# MC_stm32.net
KiCad netlist of a schematic drawn in Altium Designer
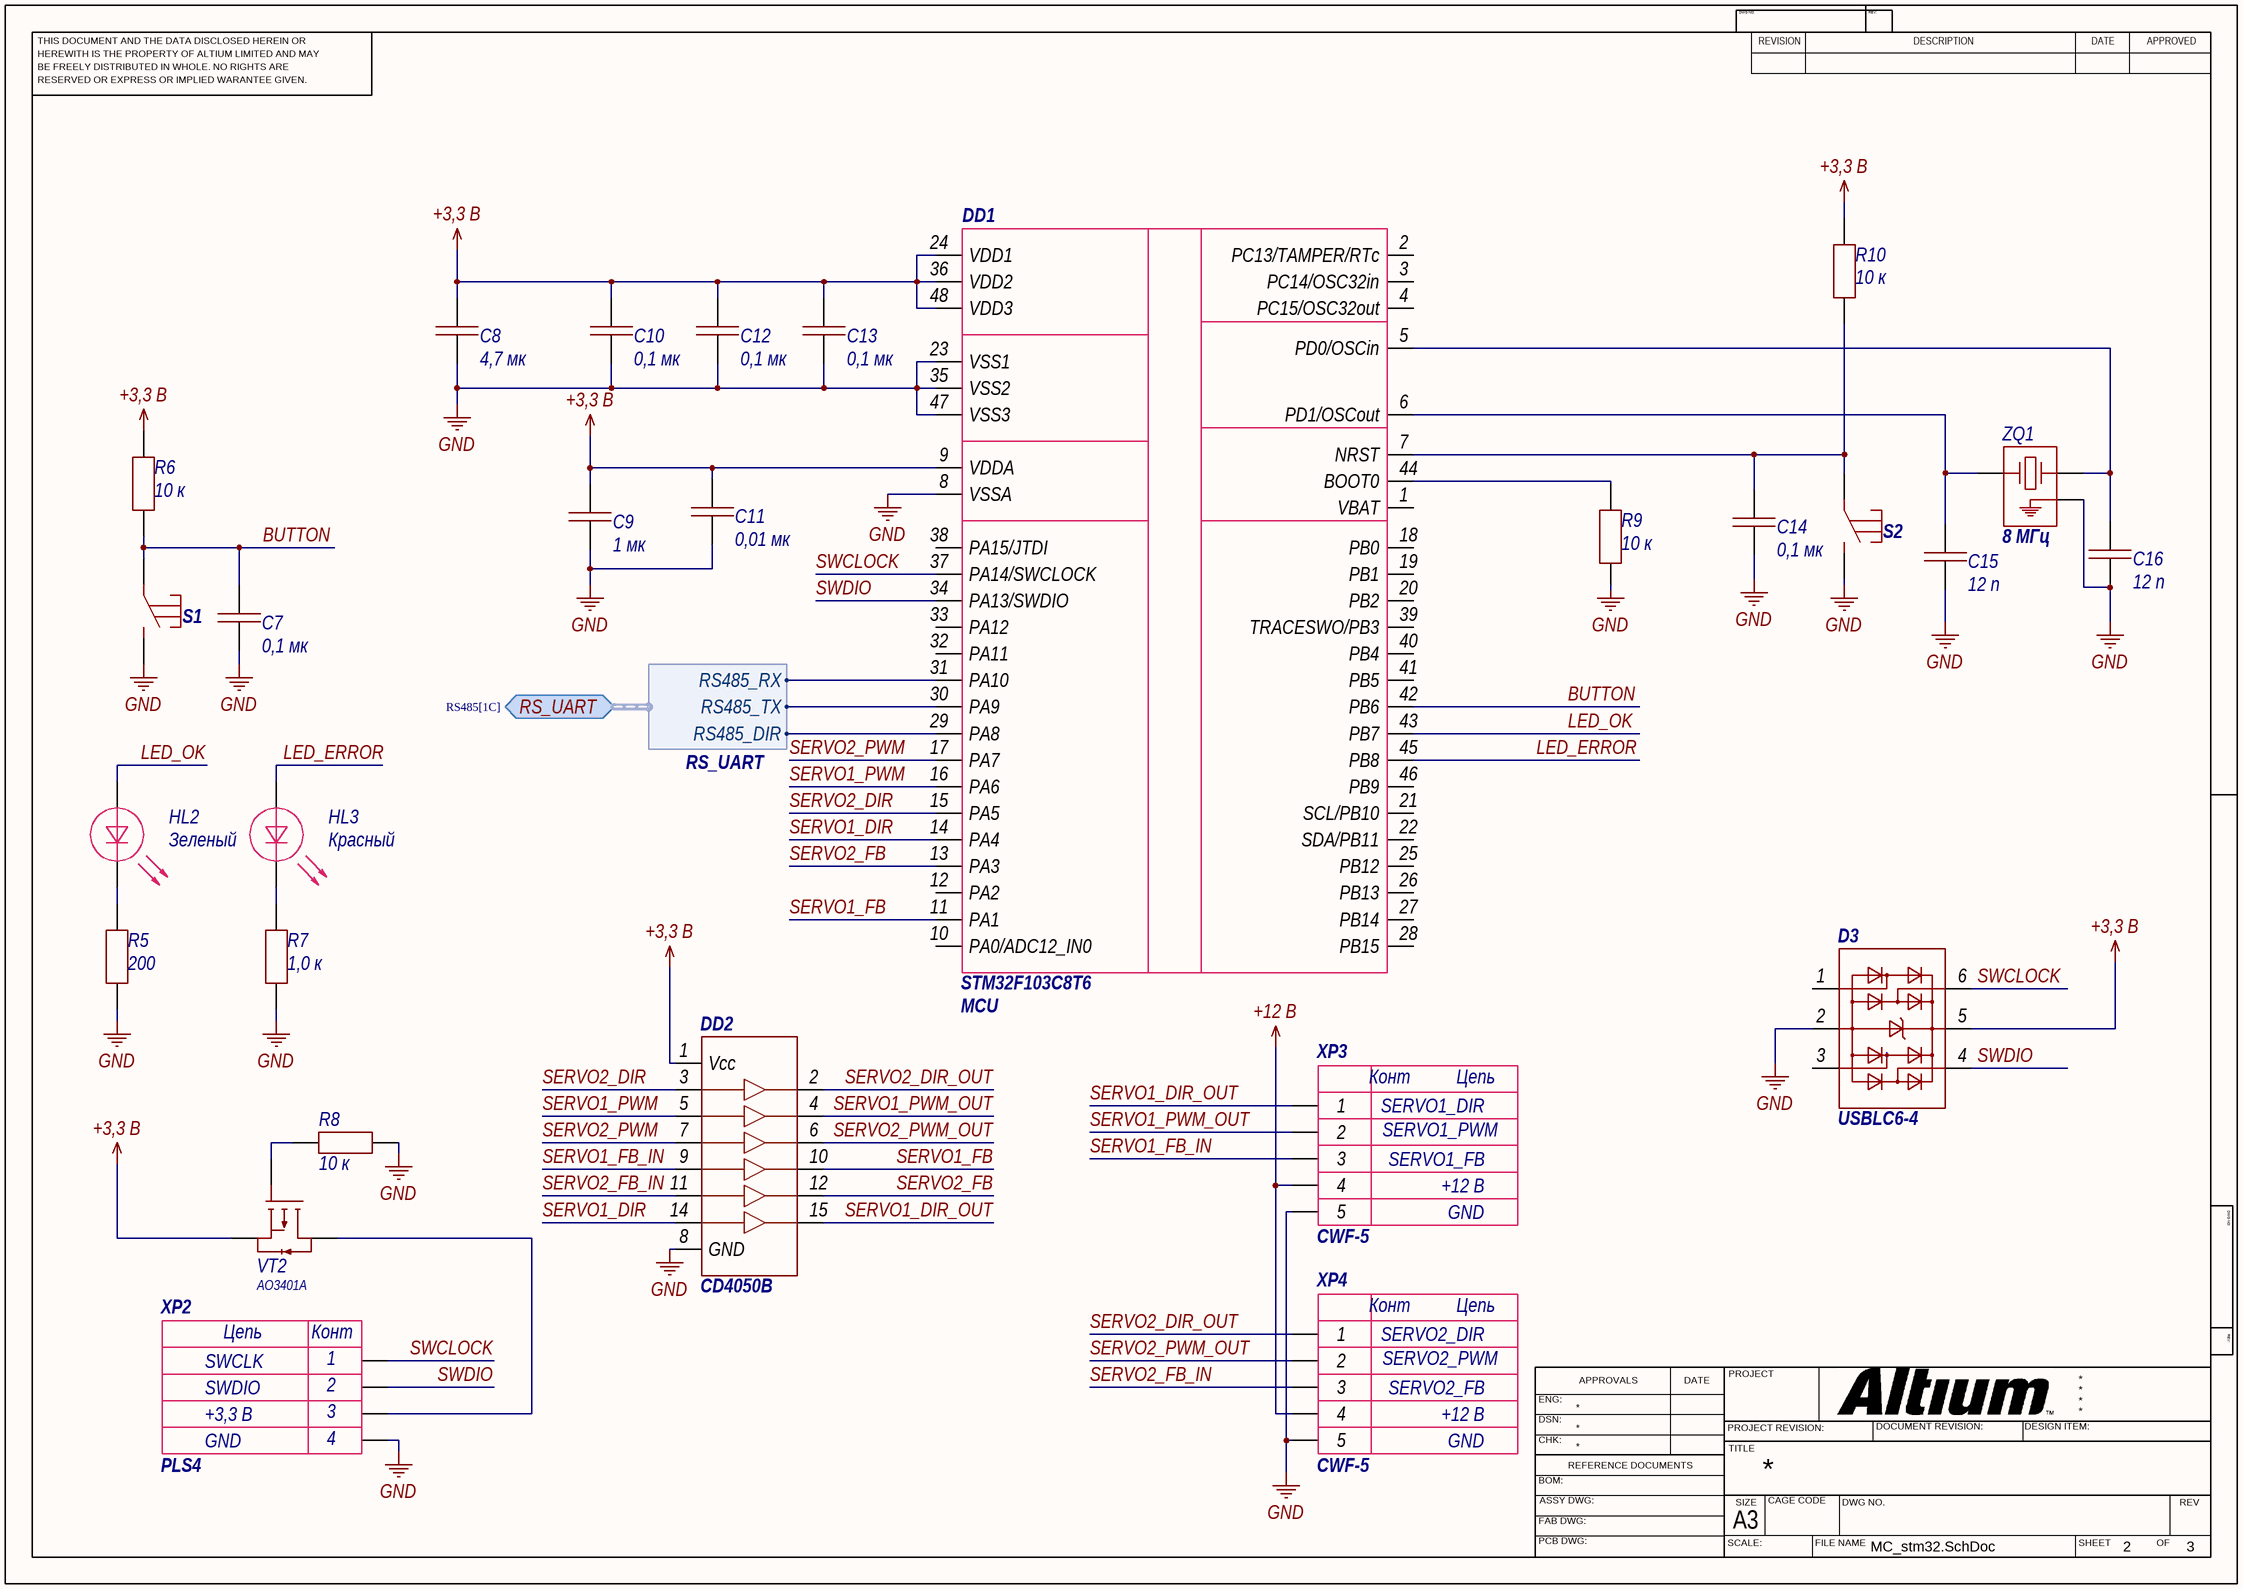
[diagram p0: MC_stm32.SchDoc]

(export (version "E")
  (design (tool "Eeschema 10.0.6"))
  (components
    (comp (ref "C7")
      (value "0,1 мк")
      (footprint "0603C")
      (description "Конденсатор")
      (fields (field (name "PART NUMBER") "Capacitor_0,1u_10_50V_X7R_0603C") (field (name "TOLERANCE") "0,1"))
      (libsource (lib "Hydrolib") (part "Capacitor"))
    )
    (comp (ref "C8")
      (value "4,7 мк")
      (footprint "1206C")
      (description "Конденсатор")
      (fields (field (name "PART NUMBER") "Capacitor_4,7u_10_50V_X7R_1206C") (field (name "TOLERANCE") "0,1"))
      (libsource (lib "Hydrolib") (part "Capacitor"))
    )
    (comp (ref "C9")
      (value "1 мк")
      (footprint "0603C")
      (description "Конденсатор")
      (fields (field (name "PART NUMBER") "Capacitor_1u_10_50V_X7R_0603C") (field (name "TOLERANCE") "0,1"))
      (libsource (lib "Hydrolib") (part "Capacitor"))
    )
    (comp (ref "C10")
      (value "0,1 мк")
      (footprint "0603C")
      (description "Конденсатор")
      (fields (field (name "PART NUMBER") "Capacitor_0,1u_10_50V_X7R_0603C") (field (name "TOLERANCE") "0,1"))
      (libsource (lib "Hydrolib") (part "Capacitor"))
    )
    (comp (ref "C11")
      (value "0,01 мк")
      (footprint "0603C")
      (description "Конденсатор")
      (fields (field (name "PART NUMBER") "Capacitor_10n_10_50V_X7R_0603C") (field (name "TOLERANCE") "0,1"))
      (libsource (lib "Hydrolib") (part "Capacitor"))
    )
    (comp (ref "C12")
      (value "0,1 мк")
      (footprint "0603C")
      (description "Конденсатор")
      (fields (field (name "PART NUMBER") "Capacitor_0,1u_10_50V_X7R_0603C") (field (name "TOLERANCE") "0,1"))
      (libsource (lib "Hydrolib") (part "Capacitor"))
    )
    (comp (ref "C13")
      (value "0,1 мк")
      (footprint "0603C")
      (description "Конденсатор")
      (fields (field (name "PART NUMBER") "Capacitor_0,1u_10_50V_X7R_0603C") (field (name "TOLERANCE") "0,1"))
      (libsource (lib "Hydrolib") (part "Capacitor"))
    )
    (comp (ref "C14")
      (value "0,1 мк")
      (footprint "0603C")
      (description "Конденсатор")
      (fields (field (name "PART NUMBER") "Capacitor_0,1u_10_50V_X7R_0603C") (field (name "TOLERANCE") "0,1"))
      (libsource (lib "Hydrolib") (part "Capacitor"))
    )
    (comp (ref "C15")
      (value "12 п")
      (footprint "0603C")
      (description "Конденсатор")
      (fields (field (name "PART NUMBER") "Capacitor"))
      (libsource (lib "Hydrolib") (part "Capacitor"))
    )
    (comp (ref "C16")
      (value "12 п")
      (footprint "0603C")
      (description "Конденсатор")
      (fields (field (name "PART NUMBER") "Capacitor"))
      (libsource (lib "Hydrolib") (part "Capacitor"))
    )
    (comp (ref "D3")
      (value "USBLC6-4")
      (footprint "SOT23-6")
      (description "Сборка защитных диодов для USB")
      (libsource (lib "Hydrolib") (part "USBLC6-4"))
    )
    (comp (ref "DD1")
      (value "STM32F103C8T6")
      (footprint "LQFP48")
      (description "Микроконтроллер")
      (fields (field (name "MANUFACTURER") "ST Microelectronics") (field (name "VALUE1") "MCU"))
      (libsource (lib "Hydrolib") (part "STM32F103C8T6"))
    )
    (comp (ref "DD2")
      (value "CD4050B")
      (footprint "SOIC-16")
      (description "Шесть буферных элементов")
      (libsource (lib "Hydrolib") (part "CD4050B"))
    )
    (comp (ref "HL2")
      (value "LED")
      (footprint "0805D")
      (description "Светодиод")
      (fields (field (name "COLOR") "Зеленый"))
      (libsource (lib "Hydrolib") (part "LED"))
    )
    (comp (ref "HL3")
      (value "LED")
      (footprint "0805D")
      (description "Светодиод")
      (fields (field (name "COLOR") "Красный"))
      (libsource (lib "Hydrolib") (part "LED"))
    )
    (comp (ref "R5")
      (value "200")
      (footprint "0603R")
      (description "Резистор номиналом 200 Ом и точностью 1%")
      (fields (field (name "PART NUMBER") "Resistor_200_1_0603") (field (name "TOLERANCE") "1%"))
      (libsource (lib "") (part "Resistor_1"))
    )
    (comp (ref "R6")
      (value "10 к")
      (footprint "0603R")
      (description "Резистор номиналом 10 кОм и точностью 1%")
      (fields (field (name "PART NUMBER") "Resistor_10k_1_0603") (field (name "TOLERANCE") "1%"))
      (libsource (lib "") (part "Resistor_1"))
    )
    (comp (ref "R7")
      (value "1,0 к")
      (footprint "0603R")
      (description "Резистор номиналом 1,0 кОм и точностью 1%")
      (fields (field (name "PART NUMBER") "Resistor_1.0k_1_0603") (field (name "TOLERANCE") "1%"))
      (libsource (lib "") (part "Resistor_1"))
    )
    (comp (ref "R8")
      (value "10 к")
      (footprint "0603R")
      (description "Резистор номиналом 10 кОм и точностью 1%")
      (fields (field (name "PART NUMBER") "Resistor_10k_1_0603") (field (name "TOLERANCE") "1%"))
      (libsource (lib "Hydrolib") (part "Resistor"))
    )
    (comp (ref "R9")
      (value "10 к")
      (footprint "0603R")
      (description "Резистор номиналом 10 кОм и точностью 1%")
      (fields (field (name "PART NUMBER") "Resistor_10k_1_0603") (field (name "TOLERANCE") "1%"))
      (libsource (lib "") (part "Resistor_1"))
    )
    (comp (ref "R10")
      (value "10 к")
      (footprint "0603R")
      (description "Резистор номиналом 10 кОм и точностью 1%")
      (fields (field (name "PART NUMBER") "Resistor_10k_1_0603") (field (name "TOLERANCE") "1%"))
      (libsource (lib "") (part "Resistor_2"))
    )
    (comp (ref "S1")
      (value "Tact_button")
      (footprint "Button_SMD_10mm")
      (description "Тактовая кнопка")
      (libsource (lib "Hydrolib") (part "Tact_button"))
    )
    (comp (ref "S2")
      (value "Tact_button")
      (footprint "Button_SMD_10mm")
      (description "Тактовая кнопка")
      (libsource (lib "Hydrolib") (part "Tact_button"))
    )
    (comp (ref "VT2")
      (value "AO3401A")
      (footprint "SOT23-3")
      (description "P-канальный MOSFET")
      (libsource (lib "Hydrolib") (part "MOSFET P-channel 2"))
    )
    (comp (ref "XP2")
      (value "PLS4")
      (footprint "PLS4")
      (description "Гребенка 4 пина")
      (fields
        (field (name "VALUE3") "+3,3 В")
        (field (name "VALUE2") "SWDIO")
        (field (name "VALUE4") "GND")
        (field (name "VALUE1") "SWCLK")
      )
      (libsource (lib "Hydrolib") (part "Conn_4pin"))
    )
    (comp (ref "XP3")
      (value "CWF-5")
      (footprint "CWF-5")
      (description "5-пиновый разъем с ключом")
      (fields
        (field (name "SERVO1_DIR") "SERVO1_DIR")
        (field (name "VALUE2") "SERVO1_PWM")
        (field (name "VALUE3") "SERVO1_FB")
        (field (name "VALUE4") "+12 В")
        (field (name "VALUE5") "GND")
      )
      (libsource (lib "Hydrolib") (part "Conn_5pin"))
    )
    (comp (ref "XP4")
      (value "CWF-5")
      (footprint "CWF-5")
      (description "5-пиновый разъем с ключом")
      (fields
        (field (name "VALUE1") "SERVO2_DIR")
        (field (name "VALUE2") "SERVO2_PWM")
        (field (name "VALUE3") "SERVO2_FB")
        (field (name "VALUE4") "+12 В")
        (field (name "VALUE5") "GND")
      )
      (libsource (lib "Hydrolib") (part "Conn_5pin"))
    )
    (comp (ref "ZQ1")
      (value "8 МГц")
      (footprint "QSMD3.2x2.5")
      (description "WTL3M85421FO, Резонатор кварцевый 8МГц, 10PPM при 25°C, 20PPM при -40°С+85°C, 400Ом, 12пФ")
      (fields (field (name "PART NUMBER") "XTAL_GND"))
      (libsource (lib "Hydrolib") (part "XTAL_GND"))
    )
  )
  (nets
    (net (code "2") (name "+3,3 В") (class "Default")
      (node (ref "C10") (pin "2") (pinfunction "2_2") (pintype "passive"))
      (node (ref "C11") (pin "2") (pinfunction "2_2") (pintype "passive"))
      (node (ref "C12") (pin "2") (pinfunction "2_2") (pintype "passive"))
      (node (ref "C13") (pin "2") (pinfunction "2_2") (pintype "passive"))
      (node (ref "C8") (pin "1") (pinfunction "1_1") (pintype "passive"))
      (node (ref "C9") (pin "2") (pinfunction "2_2") (pintype "passive"))
      (node (ref "D3") (pin "5") (pinfunction "13_5") (pintype "passive"))
      (node (ref "DD1") (pin "24") (pinfunction "VDD1_24") (pintype "passive"))
      (node (ref "DD1") (pin "36") (pinfunction "VDD2_36") (pintype "passive"))
      (node (ref "DD1") (pin "48") (pinfunction "VDD3_48") (pintype "passive"))
      (node (ref "DD1") (pin "9") (pinfunction "VDDA_9") (pintype "passive"))
      (node (ref "DD2") (pin "1") (pinfunction "Vcc_1") (pintype "passive"))
      (node (ref "R10") (pin "2") (pinfunction "2_2") (pintype "passive"))
      (node (ref "R6") (pin "1") (pinfunction "1_1") (pintype "passive"))
      (node (ref "VT2") (pin "2") (pinfunction "2_2") (pintype "passive"))
    )
    (net (code "3") (name "+12 В") (class "Default")
      (node (ref "XP3") (pin "4") (pinfunction "4_4") (pintype "passive"))
      (node (ref "XP4") (pin "4") (pinfunction "4_4") (pintype "passive"))
    )
    (net (code "4") (name "/BUTTON") (class "Default")
      (node (ref "C7") (pin "2") (pinfunction "2_2") (pintype "passive"))
      (node (ref "DD1") (pin "42") (pinfunction "PB6_42") (pintype "passive"))
      (node (ref "R6") (pin "2") (pinfunction "2_2") (pintype "passive"))
      (node (ref "S1") (pin "1") (pinfunction "1_1") (pintype "passive"))
    )
    (net (code "5") (name "/LED_ERROR") (class "Default")
      (node (ref "DD1") (pin "45") (pinfunction "PB8_45") (pintype "passive"))
      (node (ref "HL3") (pin "1") (pinfunction "1_1") (pintype "passive"))
    )
    (net (code "6") (name "/LED_OK") (class "Default")
      (node (ref "DD1") (pin "43") (pinfunction "PB7_43") (pintype "passive"))
      (node (ref "HL2") (pin "1") (pinfunction "1_1") (pintype "passive"))
    )
    (net (code "7") (name "/RS485_DIR") (class "Default")
      (node (ref "DD1") (pin "29") (pinfunction "PA8_29") (pintype "passive"))
    )
    (net (code "8") (name "/RS485_RX") (class "Default")
      (node (ref "DD1") (pin "31") (pinfunction "PA10_31") (pintype "passive"))
    )
    (net (code "9") (name "/RS485_TX") (class "Default")
      (node (ref "DD1") (pin "30") (pinfunction "PA9_30") (pintype "passive"))
    )
    (net (code "10") (name "/SERVO1_DIR") (class "Default")
      (node (ref "DD1") (pin "14") (pinfunction "PA4_14") (pintype "passive"))
      (node (ref "DD2") (pin "14") (pinfunction "A6_14") (pintype "passive"))
    )
    (net (code "11") (name "/SERVO1_DIR_OUT") (class "Default")
      (node (ref "DD2") (pin "15") (pinfunction "Y6_15") (pintype "passive"))
      (node (ref "XP3") (pin "1") (pinfunction "1_1") (pintype "passive"))
    )
    (net (code "12") (name "/SERVO1_FB") (class "Default")
      (node (ref "DD1") (pin "11") (pinfunction "PA1_11") (pintype "passive"))
      (node (ref "DD2") (pin "10") (pinfunction "Y10_10") (pintype "passive"))
    )
    (net (code "13") (name "/SERVO1_FB_IN") (class "Default")
      (node (ref "DD2") (pin "9") (pinfunction "A4_9") (pintype "passive"))
      (node (ref "XP3") (pin "3") (pinfunction "3_3") (pintype "passive"))
    )
    (net (code "14") (name "/SERVO1_PWM") (class "Default")
      (node (ref "DD1") (pin "16") (pinfunction "PA6_16") (pintype "passive"))
      (node (ref "DD2") (pin "5") (pinfunction "A2_5") (pintype "passive"))
    )
    (net (code "15") (name "/SERVO1_PWM_OUT") (class "Default")
      (node (ref "DD2") (pin "4") (pinfunction "Y2_4") (pintype "passive"))
      (node (ref "XP3") (pin "2") (pinfunction "2_2") (pintype "passive"))
    )
    (net (code "16") (name "/SERVO2_DIR") (class "Default")
      (node (ref "DD1") (pin "15") (pinfunction "PA5_15") (pintype "passive"))
      (node (ref "DD2") (pin "3") (pinfunction "A1_3") (pintype "passive"))
    )
    (net (code "17") (name "/SERVO2_DIR_OUT") (class "Default")
      (node (ref "DD2") (pin "2") (pinfunction "Y1_2") (pintype "passive"))
      (node (ref "XP4") (pin "1") (pinfunction "1_1") (pintype "passive"))
    )
    (net (code "18") (name "/SERVO2_FB") (class "Default")
      (node (ref "DD1") (pin "13") (pinfunction "PA3_13") (pintype "passive"))
      (node (ref "DD2") (pin "12") (pinfunction "Y5_12") (pintype "passive"))
    )
    (net (code "19") (name "/SERVO2_FB_IN") (class "Default")
      (node (ref "DD2") (pin "11") (pinfunction "A5_11") (pintype "passive"))
      (node (ref "XP4") (pin "3") (pinfunction "3_3") (pintype "passive"))
    )
    (net (code "20") (name "/SERVO2_PWM") (class "Default")
      (node (ref "DD1") (pin "17") (pinfunction "PA7_17") (pintype "passive"))
      (node (ref "DD2") (pin "7") (pinfunction "A3_7") (pintype "passive"))
    )
    (net (code "21") (name "/SERVO2_PWM_OUT") (class "Default")
      (node (ref "DD2") (pin "6") (pinfunction "Y3_6") (pintype "passive"))
      (node (ref "XP4") (pin "2") (pinfunction "2_2") (pintype "passive"))
    )
    (net (code "22") (name "/SWCLOCK") (class "Default")
      (node (ref "D3") (pin "6") (pinfunction "14_6") (pintype "passive"))
      (node (ref "DD1") (pin "37") (pinfunction "PA14/SWCLOCK_37") (pintype "passive"))
      (node (ref "XP2") (pin "1") (pinfunction "1_1") (pintype "passive"))
    )
    (net (code "23") (name "/SWDIO") (class "Default")
      (node (ref "D3") (pin "4") (pinfunction "12_4") (pintype "passive"))
      (node (ref "DD1") (pin "34") (pinfunction "PA13/SWDIO_34") (pintype "passive"))
      (node (ref "XP2") (pin "2") (pinfunction "2_2") (pintype "passive"))
    )
    (net (code "25") (name "GND") (class "Default")
      (node (ref "C10") (pin "1") (pinfunction "1_1") (pintype "passive"))
      (node (ref "C11") (pin "1") (pinfunction "1_1") (pintype "passive"))
      (node (ref "C12") (pin "1") (pinfunction "1_1") (pintype "passive"))
      (node (ref "C13") (pin "1") (pinfunction "1_1") (pintype "passive"))
      (node (ref "C14") (pin "1") (pinfunction "1_1") (pintype "passive"))
      (node (ref "C15") (pin "2") (pinfunction "2_2") (pintype "passive"))
      (node (ref "C16") (pin "2") (pinfunction "2_2") (pintype "passive"))
      (node (ref "C7") (pin "1") (pinfunction "1_1") (pintype "passive"))
      (node (ref "C8") (pin "2") (pinfunction "2_2") (pintype "passive"))
      (node (ref "C9") (pin "1") (pinfunction "1_1") (pintype "passive"))
      (node (ref "D3") (pin "2") (pinfunction "10_2") (pintype "passive"))
      (node (ref "DD1") (pin "23") (pinfunction "VSS1_23") (pintype "passive"))
      (node (ref "DD1") (pin "35") (pinfunction "VSS2_35") (pintype "passive"))
      (node (ref "DD1") (pin "47") (pinfunction "VSS3_47") (pintype "passive"))
      (node (ref "DD1") (pin "8") (pinfunction "VSSA_8") (pintype "passive"))
      (node (ref "DD2") (pin "8") (pinfunction "GND_8") (pintype "passive"))
      (node (ref "R5") (pin "2") (pinfunction "2_2") (pintype "passive"))
      (node (ref "R7") (pin "2") (pinfunction "2_2") (pintype "passive"))
      (node (ref "R8") (pin "2") (pinfunction "2_2") (pintype "passive"))
      (node (ref "R9") (pin "2") (pinfunction "2_2") (pintype "passive"))
      (node (ref "S1") (pin "2") (pinfunction "2_2") (pintype "passive"))
      (node (ref "S2") (pin "2") (pinfunction "2_2") (pintype "passive"))
      (node (ref "XP2") (pin "4") (pinfunction "4_4") (pintype "passive"))
      (node (ref "XP3") (pin "5") (pinfunction "5_5") (pintype "passive"))
      (node (ref "XP4") (pin "5") (pinfunction "5_5") (pintype "passive"))
      (node (ref "ZQ1") (pin "3") (pinfunction "3_3") (pintype "passive"))
    )
    (net (code "26") (name "Net-(DD1-BOOT0)") (class "Default")
      (node (ref "DD1") (pin "44") (pinfunction "BOOT0_44") (pintype "passive"))
      (node (ref "R9") (pin "1") (pinfunction "1_1") (pintype "passive"))
    )
    (net (code "27") (name "Net-(DD1-NRST)") (class "Default")
      (node (ref "C14") (pin "2") (pinfunction "2_2") (pintype "passive"))
      (node (ref "DD1") (pin "7") (pinfunction "NRST_7") (pintype "passive"))
      (node (ref "R10") (pin "1") (pinfunction "1_1") (pintype "passive"))
      (node (ref "S2") (pin "1") (pinfunction "1_1") (pintype "passive"))
    )
    (net (code "28") (name "Net-(DD1-PD0{slash}OSCin)") (class "Default")
      (node (ref "C16") (pin "1") (pinfunction "1_1") (pintype "passive"))
      (node (ref "DD1") (pin "5") (pinfunction "PD0/OSCin_5") (pintype "passive"))
      (node (ref "ZQ1") (pin "2") (pinfunction "2_2") (pintype "passive"))
    )
    (net (code "29") (name "Net-(DD1-PD1{slash}OSCout)") (class "Default")
      (node (ref "C15") (pin "1") (pinfunction "1_1") (pintype "passive"))
      (node (ref "DD1") (pin "6") (pinfunction "PD1/OSCout_6") (pintype "passive"))
      (node (ref "ZQ1") (pin "1") (pinfunction "1_1") (pintype "passive"))
    )
    (net (code "30") (name "Net-(HL2-Pad2)") (class "Default")
      (node (ref "HL2") (pin "2") (pinfunction "2_2") (pintype "passive"))
      (node (ref "R5") (pin "1") (pinfunction "1_1") (pintype "passive"))
    )
    (net (code "31") (name "Net-(HL3-Pad2)") (class "Default")
      (node (ref "HL3") (pin "2") (pinfunction "2_2") (pintype "passive"))
      (node (ref "R7") (pin "1") (pinfunction "1_1") (pintype "passive"))
    )
    (net (code "32") (name "Net-(R8-Pad1)") (class "Default")
      (node (ref "R8") (pin "1") (pinfunction "1_1") (pintype "passive"))
      (node (ref "VT2") (pin "1") (pinfunction "1_1") (pintype "passive"))
    )
    (net (code "33") (name "Net-(VT2-Pad3)") (class "Default")
      (node (ref "VT2") (pin "3") (pinfunction "3_3") (pintype "passive"))
      (node (ref "XP2") (pin "3") (pinfunction "3_3") (pintype "passive"))
    )
    (net (code "34") (name "unconnected-(D3-9-Pad1)") (class "Default")
      (node (ref "D3") (pin "1") (pinfunction "9_1") (pintype "passive"))
    )
    (net (code "35") (name "unconnected-(D3-11-Pad3)") (class "Default")
      (node (ref "D3") (pin "3") (pinfunction "11_3") (pintype "passive"))
    )
    (net (code "36") (name "unconnected-(DD1-PA0{slash}ADC12_IN0-Pad10)") (class "Default")
      (node (ref "DD1") (pin "10") (pinfunction "PA0/ADC12_IN0_10") (pintype "passive"))
    )
    (net (code "37") (name "unconnected-(DD1-PA2-Pad12)") (class "Default")
      (node (ref "DD1") (pin "12") (pinfunction "PA2_12") (pintype "passive"))
    )
    (net (code "38") (name "unconnected-(DD1-PA11-Pad32)") (class "Default")
      (node (ref "DD1") (pin "32") (pinfunction "PA11_32") (pintype "passive"))
    )
    (net (code "39") (name "unconnected-(DD1-PA12-Pad33)") (class "Default")
      (node (ref "DD1") (pin "33") (pinfunction "PA12_33") (pintype "passive"))
    )
    (net (code "40") (name "unconnected-(DD1-PA15{slash}JTDI-Pad38)") (class "Default")
      (node (ref "DD1") (pin "38") (pinfunction "PA15/JTDI_38") (pintype "passive"))
    )
    (net (code "41") (name "unconnected-(DD1-PB0-Pad18)") (class "Default")
      (node (ref "DD1") (pin "18") (pinfunction "PB0_18") (pintype "passive"))
    )
    (net (code "42") (name "unconnected-(DD1-PB1-Pad19)") (class "Default")
      (node (ref "DD1") (pin "19") (pinfunction "PB1_19") (pintype "passive"))
    )
    (net (code "43") (name "unconnected-(DD1-PB2-Pad20)") (class "Default")
      (node (ref "DD1") (pin "20") (pinfunction "PB2_20") (pintype "passive"))
    )
    (net (code "44") (name "unconnected-(DD1-PB4-Pad40)") (class "Default")
      (node (ref "DD1") (pin "40") (pinfunction "PB4_40") (pintype "passive"))
    )
    (net (code "45") (name "unconnected-(DD1-PB5-Pad41)") (class "Default")
      (node (ref "DD1") (pin "41") (pinfunction "PB5_41") (pintype "passive"))
    )
    (net (code "46") (name "unconnected-(DD1-PB9-Pad46)") (class "Default")
      (node (ref "DD1") (pin "46") (pinfunction "PB9_46") (pintype "passive"))
    )
    (net (code "47") (name "unconnected-(DD1-PB12-Pad25)") (class "Default")
      (node (ref "DD1") (pin "25") (pinfunction "PB12_25") (pintype "passive"))
    )
    (net (code "48") (name "unconnected-(DD1-PB13-Pad26)") (class "Default")
      (node (ref "DD1") (pin "26") (pinfunction "PB13_26") (pintype "passive"))
    )
    (net (code "49") (name "unconnected-(DD1-PB14-Pad27)") (class "Default")
      (node (ref "DD1") (pin "27") (pinfunction "PB14_27") (pintype "passive"))
    )
    (net (code "50") (name "unconnected-(DD1-PB15-Pad28)") (class "Default")
      (node (ref "DD1") (pin "28") (pinfunction "PB15_28") (pintype "passive"))
    )
    (net (code "51") (name "unconnected-(DD1-PC13{slash}TAMPER{slash}RTc-Pad2)") (class "Default")
      (node (ref "DD1") (pin "2") (pinfunction "PC13/TAMPER/RTc_2") (pintype "passive"))
    )
    (net (code "52") (name "unconnected-(DD1-PC14{slash}OSC32in-Pad3)") (class "Default")
      (node (ref "DD1") (pin "3") (pinfunction "PC14/OSC32in_3") (pintype "passive"))
    )
    (net (code "53") (name "unconnected-(DD1-PC15{slash}OSC32out-Pad4)") (class "Default")
      (node (ref "DD1") (pin "4") (pinfunction "PC15/OSC32out_4") (pintype "passive"))
    )
    (net (code "54") (name "unconnected-(DD1-SCL{slash}PB10-Pad21)") (class "Default")
      (node (ref "DD1") (pin "21") (pinfunction "SCL/PB10_21") (pintype "passive"))
    )
    (net (code "55") (name "unconnected-(DD1-SDA{slash}PB11-Pad22)") (class "Default")
      (node (ref "DD1") (pin "22") (pinfunction "SDA/PB11_22") (pintype "passive"))
    )
    (net (code "56") (name "unconnected-(DD1-TRACESWO{slash}PB3-Pad39)") (class "Default")
      (node (ref "DD1") (pin "39") (pinfunction "TRACESWO/PB3_39") (pintype "passive"))
    )
    (net (code "57") (name "unconnected-(DD1-VBAT-Pad1)") (class "Default")
      (node (ref "DD1") (pin "1") (pinfunction "VBAT_1") (pintype "passive"))
    )
  )
)
